# LowPassFilter.net
KiCad netlist of a schematic drawn in Altium Designer
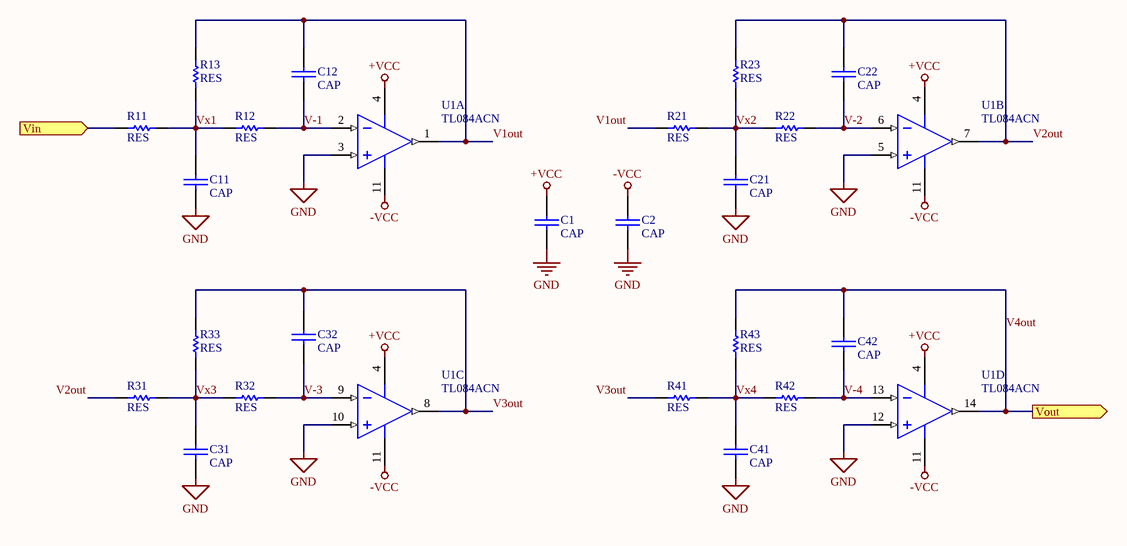
[diagram p0: LowPassFilter.SchDoc]

(export (version "E")
  (design (tool "Eeschema 10.0.6"))
  (components
    (comp (ref "C1") (value "CAP") (footprint "CAP200") (libsource (lib "Schematics") (part "CAP")))
    (comp (ref "C2") (value "CAP") (footprint "CAP200") (libsource (lib "Schematics") (part "CAP")))
    (comp (ref "C11") (value "CAP") (footprint "0805") (libsource (lib "Schematics") (part "CAP")))
    (comp (ref "C12") (value "CAP") (footprint "0805") (libsource (lib "Schematics") (part "CAP")))
    (comp (ref "C21") (value "CAP") (footprint "0805") (libsource (lib "Schematics") (part "CAP")))
    (comp (ref "C22") (value "CAP") (footprint "0805") (libsource (lib "Schematics") (part "CAP")))
    (comp (ref "C31") (value "CAP") (footprint "0805") (libsource (lib "Schematics") (part "CAP")))
    (comp (ref "C32") (value "CAP") (footprint "0805") (libsource (lib "Schematics") (part "CAP")))
    (comp (ref "C41") (value "CAP") (footprint "0805") (libsource (lib "Schematics") (part "CAP")))
    (comp (ref "C42") (value "CAP") (footprint "0805") (libsource (lib "Schematics") (part "CAP")))
    (comp (ref "R11") (value "RES") (footprint "0805") (libsource (lib "Schematics") (part "RES")))
    (comp (ref "R12") (value "RES") (footprint "0805") (libsource (lib "Schematics") (part "RES")))
    (comp (ref "R13") (value "RES") (footprint "0805") (libsource (lib "Schematics") (part "RES")))
    (comp (ref "R21") (value "RES") (footprint "0805") (libsource (lib "Schematics") (part "RES")))
    (comp (ref "R22") (value "RES") (footprint "0805") (libsource (lib "Schematics") (part "RES")))
    (comp (ref "R23") (value "RES") (footprint "0805") (libsource (lib "Schematics") (part "RES")))
    (comp (ref "R31") (value "RES") (footprint "0805") (libsource (lib "Schematics") (part "RES")))
    (comp (ref "R32") (value "RES") (footprint "0805") (libsource (lib "Schematics") (part "RES")))
    (comp (ref "R33") (value "RES") (footprint "0805") (libsource (lib "Schematics") (part "RES")))
    (comp (ref "R41") (value "RES") (footprint "0805") (libsource (lib "Schematics") (part "RES")))
    (comp (ref "R42") (value "RES") (footprint "0805") (libsource (lib "Schematics") (part "RES")))
    (comp (ref "R43") (value "RES") (footprint "0805") (libsource (lib "Schematics") (part "RES")))
    (comp (ref "U1")
      (value "TL084ACN")
      (footprint "TI-N14")
      (description "JFET-Input Operational Amplifier, 7 to 36 V, 0 to 70 degC, 14-pin DIP (N14), Pb-Free (RoHS)")
      (fields (field (name "MANUFACTURER") "Texas Instruments"))
      (libsource (lib "TI Amplifiers and Linear Operational Amplifier General Purpose") (part "TL084ACN"))
    )
  )
  (nets
    (net (code "1") (name "+VCC") (class "Default")
      (node (ref "C1") (pin "1") (pinfunction "1_1") (pintype "passive"))
      (node (ref "U1") (pin "4") (pinfunction "VCC+_4") (pintype "power_in"))
    )
    (net (code "2") (name "-VCC") (class "Default")
      (node (ref "C2") (pin "1") (pinfunction "1_1") (pintype "passive"))
      (node (ref "U1") (pin "11") (pinfunction "VCC-_11") (pintype "power_in"))
    )
    (net (code "3") (name "/V-1") (class "Default")
      (node (ref "C12") (pin "2") (pinfunction "2_2") (pintype "passive"))
      (node (ref "R12") (pin "2") (pinfunction "2_2") (pintype "passive"))
      (node (ref "U1") (pin "2") (pinfunction "IN1-_2") (pintype "input"))
    )
    (net (code "4") (name "/V-2") (class "Default")
      (node (ref "C22") (pin "2") (pinfunction "2_2") (pintype "passive"))
      (node (ref "R22") (pin "2") (pinfunction "2_2") (pintype "passive"))
      (node (ref "U1") (pin "6") (pinfunction "IN2-_6") (pintype "input"))
    )
    (net (code "5") (name "/V-3") (class "Default")
      (node (ref "C32") (pin "2") (pinfunction "2_2") (pintype "passive"))
      (node (ref "R32") (pin "2") (pinfunction "2_2") (pintype "passive"))
      (node (ref "U1") (pin "9") (pinfunction "IN3-_9") (pintype "input"))
    )
    (net (code "6") (name "/V-4") (class "Default")
      (node (ref "C42") (pin "2") (pinfunction "2_2") (pintype "passive"))
      (node (ref "R42") (pin "2") (pinfunction "2_2") (pintype "passive"))
      (node (ref "U1") (pin "13") (pinfunction "IN4-_13") (pintype "input"))
    )
    (net (code "7") (name "/V1out") (class "Default")
      (node (ref "C12") (pin "1") (pinfunction "1_1") (pintype "passive"))
      (node (ref "R13") (pin "1") (pinfunction "1_1") (pintype "passive"))
      (node (ref "R21") (pin "1") (pinfunction "1_1") (pintype "passive"))
      (node (ref "U1") (pin "1") (pinfunction "OUT1_1") (pintype "output"))
    )
    (net (code "8") (name "/V2out") (class "Default")
      (node (ref "C22") (pin "1") (pinfunction "1_1") (pintype "passive"))
      (node (ref "R23") (pin "1") (pinfunction "1_1") (pintype "passive"))
      (node (ref "R31") (pin "1") (pinfunction "1_1") (pintype "passive"))
      (node (ref "U1") (pin "7") (pinfunction "OUT2_7") (pintype "output"))
    )
    (net (code "9") (name "/V3out") (class "Default")
      (node (ref "C32") (pin "1") (pinfunction "1_1") (pintype "passive"))
      (node (ref "R33") (pin "1") (pinfunction "1_1") (pintype "passive"))
      (node (ref "R41") (pin "1") (pinfunction "1_1") (pintype "passive"))
      (node (ref "U1") (pin "8") (pinfunction "OUT3_8") (pintype "output"))
    )
    (net (code "10") (name "/V4out") (class "Default")
      (node (ref "C42") (pin "1") (pinfunction "1_1") (pintype "passive"))
      (node (ref "R43") (pin "1") (pinfunction "1_1") (pintype "passive"))
      (node (ref "U1") (pin "14") (pinfunction "OUT4_14") (pintype "output"))
    )
    (net (code "11") (name "/Vin") (class "Default")
      (node (ref "R11") (pin "1") (pinfunction "1_1") (pintype "passive"))
    )
    (net (code "12") (name "/Vx1") (class "Default")
      (node (ref "C11") (pin "1") (pinfunction "1_1") (pintype "passive"))
      (node (ref "R11") (pin "2") (pinfunction "2_2") (pintype "passive"))
      (node (ref "R12") (pin "1") (pinfunction "1_1") (pintype "passive"))
      (node (ref "R13") (pin "2") (pinfunction "2_2") (pintype "passive"))
    )
    (net (code "13") (name "/Vx2") (class "Default")
      (node (ref "C21") (pin "1") (pinfunction "1_1") (pintype "passive"))
      (node (ref "R21") (pin "2") (pinfunction "2_2") (pintype "passive"))
      (node (ref "R22") (pin "1") (pinfunction "1_1") (pintype "passive"))
      (node (ref "R23") (pin "2") (pinfunction "2_2") (pintype "passive"))
    )
    (net (code "14") (name "/Vx3") (class "Default")
      (node (ref "C31") (pin "1") (pinfunction "1_1") (pintype "passive"))
      (node (ref "R31") (pin "2") (pinfunction "2_2") (pintype "passive"))
      (node (ref "R32") (pin "1") (pinfunction "1_1") (pintype "passive"))
      (node (ref "R33") (pin "2") (pinfunction "2_2") (pintype "passive"))
    )
    (net (code "15") (name "/Vx4") (class "Default")
      (node (ref "C41") (pin "1") (pinfunction "1_1") (pintype "passive"))
      (node (ref "R41") (pin "2") (pinfunction "2_2") (pintype "passive"))
      (node (ref "R42") (pin "1") (pinfunction "1_1") (pintype "passive"))
      (node (ref "R43") (pin "2") (pinfunction "2_2") (pintype "passive"))
    )
    (net (code "16") (name "GND") (class "Default")
      (node (ref "C1") (pin "2") (pinfunction "2_2") (pintype "passive"))
      (node (ref "C11") (pin "2") (pinfunction "2_2") (pintype "passive"))
      (node (ref "C2") (pin "2") (pinfunction "2_2") (pintype "passive"))
      (node (ref "C21") (pin "2") (pinfunction "2_2") (pintype "passive"))
      (node (ref "C31") (pin "2") (pinfunction "2_2") (pintype "passive"))
      (node (ref "C41") (pin "2") (pinfunction "2_2") (pintype "passive"))
      (node (ref "U1") (pin "10") (pinfunction "IN3+_10") (pintype "input"))
      (node (ref "U1") (pin "12") (pinfunction "IN4+_12") (pintype "input"))
      (node (ref "U1") (pin "3") (pinfunction "IN1+_3") (pintype "input"))
      (node (ref "U1") (pin "5") (pinfunction "IN2+_5") (pintype "input"))
    )
  )
)
